# Sensors_and_Actuators.net
KiCad netlist of a schematic drawn in Altium Designer
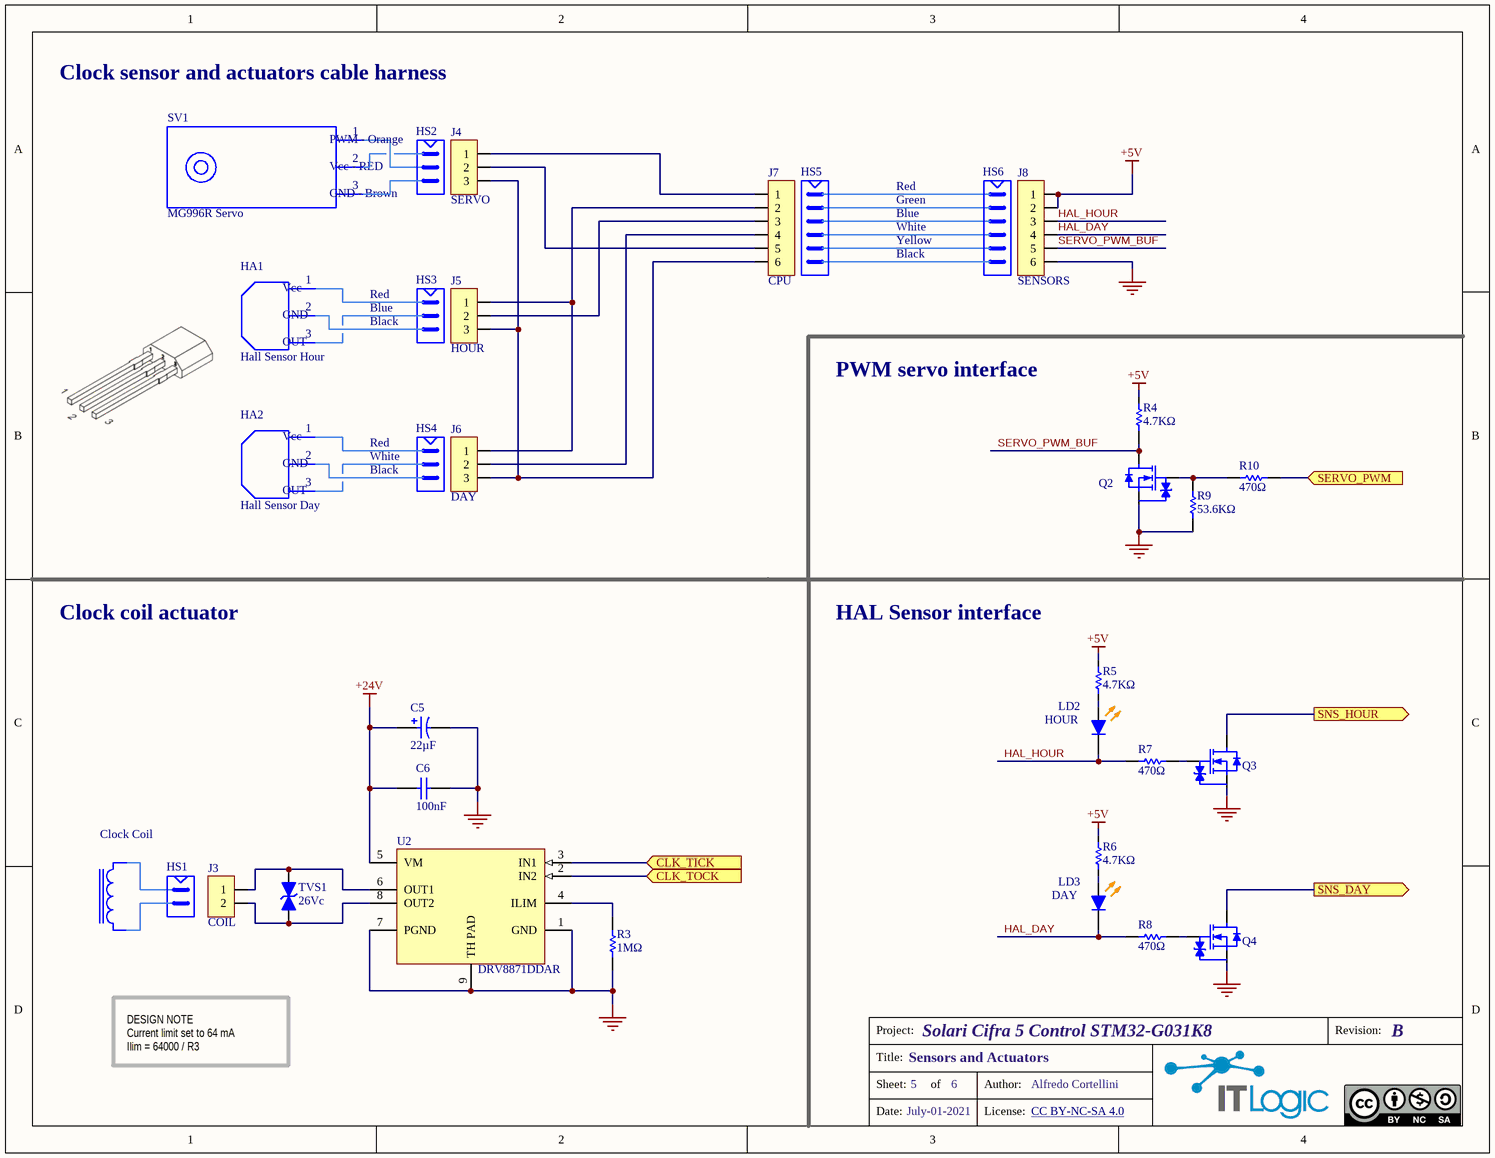
[diagram p0: Sensors and Actuators.SchDoc]

(export (version "E")
  (design (tool "Eeschema 10.0.6"))
  (components
    (comp (ref "C5")
      (value "22µF")
      (footprint "C-AE-C6-H60")
      (description "Cap Electrolytic Alu 22uF 50V 20% 165mA 2000h 105C Automotive, Case D")
      (fields
        (field (name "MANUFACTURER") "Panasonic")
        (field (name "MANUFACTURER PART NUMBER") "EEE-FK1H220P")
      )
      (libsource (lib "IT Logic Library") (part "EEE-FK1H220P"))
    )
    (comp (ref "C6")
      (value "100nF")
      (footprint "C0603-H90")
      (description "Cap 0603 Case Ceramic 100nF 50V X7R")
      (fields
        (field (name "MANUFACTURER") "TDK")
        (field (name "MANUFACTURER PART NUMBER") "CGA3E2X7R1H104K080AA")
      )
      (libsource (lib "IT Logic Library") (part "CGA3E2X7R1H104K080AA"))
    )
    (comp (ref "HA1")
      (value "Hall Sensor Hour")
      (description "Hall Effect/Magnetic Sensors 2.5 to 38 V 3-TO-92")
      (fields
        (field (name "MANUFACTURER") "Texas Instruments")
        (field (name "MANUFACTURER PART NUMBER") "DRV5023AJQLPG")
      )
      (libsource (lib "IT Logic Library") (part "DRV5023AJQLPG_MEC"))
    )
    (comp (ref "HA2")
      (value "Hall Sensor Day")
      (description "Hall Effect/Magnetic Sensors 2.5 to 38 V 3-TO-92")
      (fields
        (field (name "MANUFACTURER") "Texas Instruments")
        (field (name "MANUFACTURER PART NUMBER") "DRV5023AJQLPG")
      )
      (libsource (lib "IT Logic Library") (part "DRV5023AJQLPG_MEC"))
    )
    (comp (ref "HS1")
      (value "XHP-2")
      (description "Conn Crimp Housing, Series JST XH, 2 Circuits")
      (fields (field (name "MANUFACTURER") "JST"))
      (libsource (lib "IT Logic Library") (part "XHP-2"))
    )
    (comp (ref "HS2")
      (value "XHP-3")
      (description "Conn Crimp Housing, Series JST XH, 3 Circuits")
      (fields (field (name "MANUFACTURER") "JST"))
      (libsource (lib "IT Logic Library") (part "XHP-3"))
    )
    (comp (ref "HS3")
      (value "XHP-3")
      (description "Conn Crimp Housing, Series JST XH, 3 Circuits")
      (fields (field (name "MANUFACTURER") "JST"))
      (libsource (lib "IT Logic Library") (part "XHP-3"))
    )
    (comp (ref "HS4")
      (value "XHP-3")
      (description "Conn Crimp Housing, Series JST XH, 3 Circuits")
      (fields (field (name "MANUFACTURER") "JST"))
      (libsource (lib "IT Logic Library") (part "XHP-3"))
    )
    (comp (ref "HS5")
      (value "XHP-6")
      (description "Conn Crimp Housing, Series JST XH, 6 Circuits")
      (fields (field (name "MANUFACTURER") "JST"))
      (libsource (lib "IT Logic Library") (part "XHP-6"))
    )
    (comp (ref "HS6")
      (value "XHP-6")
      (description "Conn Crimp Housing, Series JST XH, 6 Circuits")
      (fields (field (name "MANUFACTURER") "JST"))
      (libsource (lib "IT Logic Library") (part "XHP-6"))
    )
    (comp (ref "J3")
      (value "COIL")
      (footprint "JST B2B-XH-A")
      (description "Conn Shrouded, Series JST XH, 2 Pos Header,(2.50mm) Through Hole, Vertical Tin")
      (fields
        (field (name "MANUFACTURER") "JST")
        (field (name "MANUFACTURER PART NUMBER") "B2B-XH-A(LF)(SN)")
      )
      (libsource (lib "IT Logic Library") (part "B2B-XH-A(LF)(SN)"))
    )
    (comp (ref "J4")
      (value "SERVO")
      (footprint "JST B3B-XH-A")
      (description "Conn Shrouded, Series JST XH, 3 Pos Header,(2.50mm) Through Hole, Vertical Tin")
      (fields
        (field (name "MANUFACTURER") "JST")
        (field (name "MANUFACTURER PART NUMBER") "B3B-XH-A(LF)(SN)")
      )
      (libsource (lib "IT Logic Library") (part "B3B-XH-A(LF)(SN)"))
    )
    (comp (ref "J5")
      (value "HOUR")
      (footprint "JST B3B-XH-A")
      (description "Conn Shrouded, Series JST XH, 3 Pos Header,(2.50mm) Through Hole, Vertical Tin")
      (fields
        (field (name "MANUFACTURER") "JST")
        (field (name "MANUFACTURER PART NUMBER") "B3B-XH-A(LF)(SN)")
      )
      (libsource (lib "IT Logic Library") (part "B3B-XH-A(LF)(SN)"))
    )
    (comp (ref "J6")
      (value "DAY")
      (footprint "JST B3B-XH-A")
      (description "Conn Shrouded, Series JST XH, 3 Pos Header,(2.50mm) Through Hole, Vertical Tin")
      (fields
        (field (name "MANUFACTURER") "JST")
        (field (name "MANUFACTURER PART NUMBER") "B3B-XH-A(LF)(SN)")
      )
      (libsource (lib "IT Logic Library") (part "B3B-XH-A(LF)(SN)"))
    )
    (comp (ref "J7")
      (value "CPU")
      (footprint "JST B6B-XH-A")
      (description "Conn Shrouded, Series JST XH, 6 Pos Header, (2.50mm) Through Hole, Vertical Tin")
      (fields
        (field (name "MANUFACTURER") "JST")
        (field (name "MANUFACTURER PART NUMBER") "B6B-XH-A(LF)(SN)")
      )
      (libsource (lib "IT Logic Library") (part "B6B-XH-A(LF)(SN)"))
    )
    (comp (ref "J8")
      (value "SENSORS")
      (footprint "JST B6B-XH-A")
      (description "Conn Shrouded, Series JST XH, 6 Pos Header, (2.50mm) Through Hole, Vertical Tin")
      (fields
        (field (name "MANUFACTURER") "JST")
        (field (name "MANUFACTURER PART NUMBER") "B6B-XH-A(LF)(SN)")
      )
      (libsource (lib "") (part "B6B-XH-A(LF)(SN)_1"))
    )
    (comp (ref "LD2")
      (value "HOUR")
      (footprint "LED-0805-O")
      (description "LED 0805 Top Orange 605nm 2-Pin")
      (fields
        (field (name "MANUFACTURER") "Vishay Lite-On")
        (field (name "MANUFACTURER PART NUMBER") "LTST-C170KFKT")
      )
      (libsource (lib "IT Logic Library") (part "LTST-C170KFKT"))
    )
    (comp (ref "LD3")
      (value "DAY")
      (footprint "LED-0805-O")
      (description "LED 0805 Top Orange 605nm 2-Pin")
      (fields
        (field (name "MANUFACTURER") "Vishay Lite-On")
        (field (name "MANUFACTURER PART NUMBER") "LTST-C170KFKT")
      )
      (libsource (lib "IT Logic Library") (part "LTST-C170KFKT"))
    )
    (comp (ref "Q2")
      (value "BSS138K-13")
      (footprint "SOT-23")
      (description "Mosfet N 50V Vds 20V Vgs ESD 1.4R SOT-23")
      (fields (field (name "MANUFACTURER") "Diodes"))
      (libsource (lib "IT Logic Library") (part "BSS138K-13"))
    )
    (comp (ref "Q3")
      (value "BSS138K-13")
      (footprint "SOT-23")
      (description "Mosfet N 50V Vds 20V Vgs ESD 1.4R SOT-23")
      (fields (field (name "MANUFACTURER") "Diodes"))
      (libsource (lib "IT Logic Library") (part "BSS138K-13"))
    )
    (comp (ref "Q4")
      (value "BSS138K-13")
      (footprint "SOT-23")
      (description "Mosfet N 50V Vds 20V Vgs ESD 1.4R SOT-23")
      (fields (field (name "MANUFACTURER") "Diodes"))
      (libsource (lib "IT Logic Library") (part "BSS138K-13"))
    )
    (comp (ref "R3")
      (value "1MΩ")
      (footprint "R0603-H55")
      (description "Resistor 0603 Case 1MR 1% 1/10W")
      (fields
        (field (name "MANUFACTURER") "Yageo")
        (field (name "MANUFACTURER PART NUMBER") "RC0603FR-071ML")
      )
      (libsource (lib "IT Logic Library") (part "RC0603FR-071ML"))
    )
    (comp (ref "R4")
      (value "4.7KΩ")
      (footprint "R0603-H55")
      (description "Resistor 0603 Case 4.7KR 1% 1/10W")
      (fields
        (field (name "MANUFACTURER") "Yageo")
        (field (name "MANUFACTURER PART NUMBER") "RC0603FR-074K7L")
      )
      (libsource (lib "IT Logic Library") (part "RC0603FR-074K7L"))
    )
    (comp (ref "R5")
      (value "4.7KΩ")
      (footprint "R0603-H55")
      (description "Resistor 0603 Case 4.7KR 1% 1/10W")
      (fields
        (field (name "MANUFACTURER") "Yageo")
        (field (name "MANUFACTURER PART NUMBER") "RC0603FR-074K7L")
      )
      (libsource (lib "IT Logic Library") (part "RC0603FR-074K7L"))
    )
    (comp (ref "R6")
      (value "4.7KΩ")
      (footprint "R0603-H55")
      (description "Resistor 0603 Case 4.7KR 1% 1/10W")
      (fields
        (field (name "MANUFACTURER") "Yageo")
        (field (name "MANUFACTURER PART NUMBER") "RC0603FR-074K7L")
      )
      (libsource (lib "IT Logic Library") (part "RC0603FR-074K7L"))
    )
    (comp (ref "R7")
      (value "470Ω")
      (footprint "R0603-H55")
      (description "Resistor 0603 Case 470R 1% 1/10W")
      (fields
        (field (name "MANUFACTURER") "Yageo")
        (field (name "MANUFACTURER PART NUMBER") "RC0603FR-07470RL")
      )
      (libsource (lib "IT Logic Library") (part "RC0603FR-07470RL"))
    )
    (comp (ref "R8")
      (value "470Ω")
      (footprint "R0603-H55")
      (description "Resistor 0603 Case 470R 1% 1/10W")
      (fields
        (field (name "MANUFACTURER") "Yageo")
        (field (name "MANUFACTURER PART NUMBER") "RC0603FR-07470RL")
      )
      (libsource (lib "IT Logic Library") (part "RC0603FR-07470RL"))
    )
    (comp (ref "R9")
      (value "53.6KΩ")
      (footprint "R0603-H55")
      (description "Resistor 0603 Case 53.6KR 1% 1/10W")
      (fields
        (field (name "MANUFACTURER") "Yageo")
        (field (name "MANUFACTURER PART NUMBER") "RC0603FR-0753K6L")
      )
      (libsource (lib "IT Logic Library") (part "RC0603FR-0753K6L"))
    )
    (comp (ref "R10")
      (value "470Ω")
      (footprint "R0603-H55")
      (description "Resistor 0603 Case 470R 1% 1/10W")
      (fields
        (field (name "MANUFACTURER") "Yageo")
        (field (name "MANUFACTURER PART NUMBER") "RC0603FR-07470RL")
      )
      (libsource (lib "IT Logic Library") (part "RC0603FR-07470RL"))
    )
    (comp (ref "SV1")
      (value "MG996R Servo")
      (description "Servo, High Torque, Metal Gear, Dual Ball Bearing, 120 Gegrees, Stall torque: 9.4 kgf·cm (4.8V),")
      (fields (field (name "MANUFACTURER") "Jajadeal") (field (name "MANUFACTURER PART NUMBER") "MG996R"))
      (libsource (lib "IT Logic Library") (part "MG996R"))
    )
    (comp (ref "TF1")
      (value "SXH-001T-P0.6")
      (description "Crimp Terminal, Series JST XH, Female, 22-28 AWG,")
      (fields (field (name "MANUFACTURER") "JST"))
      (libsource (lib "IT Logic Library") (part "SXH-001T-P0.6"))
    )
    (comp (ref "TF2")
      (value "SXH-001T-P0.6")
      (description "Crimp Terminal, Series JST XH, Female, 22-28 AWG,")
      (fields (field (name "MANUFACTURER") "JST"))
      (libsource (lib "IT Logic Library") (part "SXH-001T-P0.6"))
    )
    (comp (ref "TF3")
      (value "SXH-001T-P0.6")
      (description "Crimp Terminal, Series JST XH, Female, 22-28 AWG,")
      (fields (field (name "MANUFACTURER") "JST"))
      (libsource (lib "IT Logic Library") (part "SXH-001T-P0.6"))
    )
    (comp (ref "TF4")
      (value "SXH-001T-P0.6")
      (description "Crimp Terminal, Series JST XH, Female, 22-28 AWG,")
      (fields (field (name "MANUFACTURER") "JST"))
      (libsource (lib "IT Logic Library") (part "SXH-001T-P0.6"))
    )
    (comp (ref "TF5")
      (value "SXH-001T-P0.6")
      (description "Crimp Terminal, Series JST XH, Female, 22-28 AWG,")
      (fields (field (name "MANUFACTURER") "JST"))
      (libsource (lib "IT Logic Library") (part "SXH-001T-P0.6"))
    )
    (comp (ref "TF6")
      (value "SXH-001T-P0.6")
      (description "Crimp Terminal, Series JST XH, Female, 22-28 AWG,")
      (fields (field (name "MANUFACTURER") "JST"))
      (libsource (lib "IT Logic Library") (part "SXH-001T-P0.6"))
    )
    (comp (ref "TF7")
      (value "SXH-001T-P0.6")
      (description "Crimp Terminal, Series JST XH, Female, 22-28 AWG,")
      (fields (field (name "MANUFACTURER") "JST"))
      (libsource (lib "IT Logic Library") (part "SXH-001T-P0.6"))
    )
    (comp (ref "TF8")
      (value "SXH-001T-P0.6")
      (description "Crimp Terminal, Series JST XH, Female, 22-28 AWG,")
      (fields (field (name "MANUFACTURER") "JST"))
      (libsource (lib "IT Logic Library") (part "SXH-001T-P0.6"))
    )
    (comp (ref "TF9")
      (value "SXH-001T-P0.6")
      (description "Crimp Terminal, Series JST XH, Female, 22-28 AWG,")
      (fields (field (name "MANUFACTURER") "JST"))
      (libsource (lib "IT Logic Library") (part "SXH-001T-P0.6"))
    )
    (comp (ref "TF10")
      (value "SXH-001T-P0.6")
      (description "Crimp Terminal, Series JST XH, Female, 22-28 AWG,")
      (fields (field (name "MANUFACTURER") "JST"))
      (libsource (lib "IT Logic Library") (part "SXH-001T-P0.6"))
    )
    (comp (ref "TF11")
      (value "SXH-001T-P0.6")
      (description "Crimp Terminal, Series JST XH, Female, 22-28 AWG,")
      (fields (field (name "MANUFACTURER") "JST"))
      (libsource (lib "IT Logic Library") (part "SXH-001T-P0.6"))
    )
    (comp (ref "TF12")
      (value "SXH-001T-P0.6")
      (description "Crimp Terminal, Series JST XH, Female, 22-28 AWG,")
      (fields (field (name "MANUFACTURER") "JST"))
      (libsource (lib "IT Logic Library") (part "SXH-001T-P0.6"))
    )
    (comp (ref "TF13")
      (value "SXH-001T-P0.6")
      (description "Crimp Terminal, Series JST XH, Female, 22-28 AWG,")
      (fields (field (name "MANUFACTURER") "JST"))
      (libsource (lib "IT Logic Library") (part "SXH-001T-P0.6"))
    )
    (comp (ref "TF14")
      (value "SXH-001T-P0.6")
      (description "Crimp Terminal, Series JST XH, Female, 22-28 AWG,")
      (fields (field (name "MANUFACTURER") "JST"))
      (libsource (lib "IT Logic Library") (part "SXH-001T-P0.6"))
    )
    (comp (ref "TF15")
      (value "SXH-001T-P0.6")
      (description "Crimp Terminal, Series JST XH, Female, 22-28 AWG,")
      (fields (field (name "MANUFACTURER") "JST"))
      (libsource (lib "IT Logic Library") (part "SXH-001T-P0.6"))
    )
    (comp (ref "TF16")
      (value "SXH-001T-P0.6")
      (description "Crimp Terminal, Series JST XH, Female, 22-28 AWG,")
      (fields (field (name "MANUFACTURER") "JST"))
      (libsource (lib "IT Logic Library") (part "SXH-001T-P0.6"))
    )
    (comp (ref "TF17")
      (value "SXH-001T-P0.6")
      (description "Crimp Terminal, Series JST XH, Female, 22-28 AWG,")
      (fields (field (name "MANUFACTURER") "JST"))
      (libsource (lib "IT Logic Library") (part "SXH-001T-P0.6"))
    )
    (comp (ref "TF18")
      (value "SXH-001T-P0.6")
      (description "Crimp Terminal, Series JST XH, Female, 22-28 AWG,")
      (fields (field (name "MANUFACTURER") "JST"))
      (libsource (lib "IT Logic Library") (part "SXH-001T-P0.6"))
    )
    (comp (ref "TF19")
      (value "SXH-001T-P0.6")
      (description "Crimp Terminal, Series JST XH, Female, 22-28 AWG,")
      (fields (field (name "MANUFACTURER") "JST"))
      (libsource (lib "IT Logic Library") (part "SXH-001T-P0.6"))
    )
    (comp (ref "TF20")
      (value "SXH-001T-P0.6")
      (description "Crimp Terminal, Series JST XH, Female, 22-28 AWG,")
      (fields (field (name "MANUFACTURER") "JST"))
      (libsource (lib "IT Logic Library") (part "SXH-001T-P0.6"))
    )
    (comp (ref "TF21")
      (value "SXH-001T-P0.6")
      (description "Crimp Terminal, Series JST XH, Female, 22-28 AWG,")
      (fields (field (name "MANUFACTURER") "JST"))
      (libsource (lib "IT Logic Library") (part "SXH-001T-P0.6"))
    )
    (comp (ref "TF22")
      (value "SXH-001T-P0.6")
      (description "Crimp Terminal, Series JST XH, Female, 22-28 AWG,")
      (fields (field (name "MANUFACTURER") "JST"))
      (libsource (lib "IT Logic Library") (part "SXH-001T-P0.6"))
    )
    (comp (ref "TF23")
      (value "SXH-001T-P0.6")
      (description "Crimp Terminal, Series JST XH, Female, 22-28 AWG,")
      (fields (field (name "MANUFACTURER") "JST"))
      (libsource (lib "IT Logic Library") (part "SXH-001T-P0.6"))
    )
    (comp (ref "TVS1")
      (value "26Vc")
      (footprint "DO-214AC-SMA-NO POL")
      (description "TVS Diode Bidirectional 26Vs, 42.1Vc, 9.5 Amp, SMA")
      (fields (field (name "MANUFACTURER") "Littelfuse") (field (name "MANUFACTURER PART NUMBER") "SMAJ26CA"))
      (libsource (lib "IT Logic Library") (part "SMAJ26CA"))
    )
    (comp (ref "U2")
      (value "DRV8871DDAR")
      (footprint "SOIC-8-N-HT")
      (description "Motor Driver H-bridge 45V, 3.6A, Integrated current sensing SOIC-8 PowerPAD -40 to 125")
      (fields (field (name "MANUFACTURER") "Texas Instruments"))
      (libsource (lib "IT Logic Library") (part "DRV8871DDAR"))
    )
  )
  (nets
    (net (code "1") (name "+5V") (class "Default")
      (node (ref "J8") (pin "1") (pinfunction "1_1") (pintype "passive"))
      (node (ref "J8") (pin "2") (pinfunction "2_2") (pintype "passive"))
      (node (ref "R4") (pin "2") (pinfunction "2_2") (pintype "passive"))
      (node (ref "R5") (pin "2") (pinfunction "2_2") (pintype "passive"))
      (node (ref "R6") (pin "2") (pinfunction "2_2") (pintype "passive"))
    )
    (net (code "2") (name "+24V") (class "Default")
      (node (ref "C5") (pin "1") (pinfunction "1_1") (pintype "passive"))
      (node (ref "C6") (pin "1") (pinfunction "1_1") (pintype "passive"))
      (node (ref "U2") (pin "5") (pinfunction "VM_5") (pintype "power_in"))
    )
    (net (code "3") (name "/CLK_TICK") (class "Default")
      (node (ref "U2") (pin "3") (pinfunction "IN1_3") (pintype "input"))
    )
    (net (code "4") (name "/CLK_TOCK") (class "Default")
      (node (ref "U2") (pin "2") (pinfunction "IN2_2") (pintype "input"))
    )
    (net (code "5") (name "/HAL_DAY") (class "Default")
      (node (ref "J8") (pin "4") (pinfunction "4_4") (pintype "passive"))
      (node (ref "LD3") (pin "1") (pinfunction "K_1") (pintype "passive"))
      (node (ref "R8") (pin "1") (pinfunction "1_1") (pintype "passive"))
    )
    (net (code "6") (name "/HAL_HOUR") (class "Default")
      (node (ref "J8") (pin "3") (pinfunction "3_3") (pintype "passive"))
      (node (ref "LD2") (pin "1") (pinfunction "K_1") (pintype "passive"))
      (node (ref "R7") (pin "1") (pinfunction "1_1") (pintype "passive"))
    )
    (net (code "7") (name "/SERVO_PWM") (class "Default")
      (node (ref "R10") (pin "2") (pinfunction "2_2") (pintype "passive"))
    )
    (net (code "8") (name "/SERVO_PWM_BUF") (class "Default")
      (node (ref "J8") (pin "5") (pinfunction "5_5") (pintype "passive"))
      (node (ref "Q2") (pin "3") (pinfunction "D_3") (pintype "passive"))
      (node (ref "R4") (pin "1") (pinfunction "1_1") (pintype "passive"))
    )
    (net (code "9") (name "/SNS_DAY") (class "Default")
      (node (ref "Q4") (pin "3") (pinfunction "D_3") (pintype "passive"))
    )
    (net (code "10") (name "/SNS_HOUR") (class "Default")
      (node (ref "Q3") (pin "3") (pinfunction "D_3") (pintype "passive"))
    )
    (net (code "11") (name "GND") (class "Default")
      (node (ref "C5") (pin "2") (pinfunction "2_2") (pintype "passive"))
      (node (ref "C6") (pin "2") (pinfunction "2_2") (pintype "passive"))
      (node (ref "J8") (pin "6") (pinfunction "6_6") (pintype "passive"))
      (node (ref "Q2") (pin "2") (pinfunction "S_2") (pintype "passive"))
      (node (ref "Q3") (pin "2") (pinfunction "S_2") (pintype "passive"))
      (node (ref "Q4") (pin "2") (pinfunction "S_2") (pintype "passive"))
      (node (ref "R3") (pin "1") (pinfunction "1_1") (pintype "passive"))
      (node (ref "R9") (pin "1") (pinfunction "1_1") (pintype "passive"))
      (node (ref "U2") (pin "1") (pinfunction "GND_1") (pintype "power_in"))
      (node (ref "U2") (pin "7") (pinfunction "PGND_7") (pintype "power_in"))
      (node (ref "U2") (pin "9") (pinfunction "TH_PAD_9") (pintype "power_in"))
    )
    (net (code "12") (name "Net-(J4-Pad1)") (class "Default")
      (node (ref "J4") (pin "1") (pinfunction "1_1") (pintype "passive"))
      (node (ref "J7") (pin "1") (pinfunction "1_1") (pintype "passive"))
    )
    (net (code "13") (name "Net-(J4-Pad2)") (class "Default")
      (node (ref "J4") (pin "2") (pinfunction "2_2") (pintype "passive"))
      (node (ref "J7") (pin "5") (pinfunction "5_5") (pintype "passive"))
    )
    (net (code "14") (name "Net-(J4-Pad3)") (class "Default")
      (node (ref "J4") (pin "3") (pinfunction "3_3") (pintype "passive"))
      (node (ref "J5") (pin "3") (pinfunction "3_3") (pintype "passive"))
      (node (ref "J6") (pin "3") (pinfunction "3_3") (pintype "passive"))
      (node (ref "J7") (pin "6") (pinfunction "6_6") (pintype "passive"))
    )
    (net (code "15") (name "Net-(J5-Pad1)") (class "Default")
      (node (ref "J5") (pin "1") (pinfunction "1_1") (pintype "passive"))
      (node (ref "J6") (pin "1") (pinfunction "1_1") (pintype "passive"))
      (node (ref "J7") (pin "2") (pinfunction "2_2") (pintype "passive"))
    )
    (net (code "16") (name "Net-(J5-Pad2)") (class "Default")
      (node (ref "J5") (pin "2") (pinfunction "2_2") (pintype "passive"))
      (node (ref "J7") (pin "3") (pinfunction "3_3") (pintype "passive"))
    )
    (net (code "17") (name "Net-(J6-Pad2)") (class "Default")
      (node (ref "J6") (pin "2") (pinfunction "2_2") (pintype "passive"))
      (node (ref "J7") (pin "4") (pinfunction "4_4") (pintype "passive"))
    )
    (net (code "18") (name "Net-(LD2-A)") (class "Default")
      (node (ref "LD2") (pin "2") (pinfunction "A_2") (pintype "passive"))
      (node (ref "R5") (pin "1") (pinfunction "1_1") (pintype "passive"))
    )
    (net (code "19") (name "Net-(LD3-A)") (class "Default")
      (node (ref "LD3") (pin "2") (pinfunction "A_2") (pintype "passive"))
      (node (ref "R6") (pin "1") (pinfunction "1_1") (pintype "passive"))
    )
    (net (code "20") (name "Net-(Q2-G)") (class "Default")
      (node (ref "Q2") (pin "1") (pinfunction "G_1") (pintype "passive"))
      (node (ref "R10") (pin "1") (pinfunction "1_1") (pintype "passive"))
      (node (ref "R9") (pin "2") (pinfunction "2_2") (pintype "passive"))
    )
    (net (code "21") (name "Net-(Q3-G)") (class "Default")
      (node (ref "Q3") (pin "1") (pinfunction "G_1") (pintype "passive"))
      (node (ref "R7") (pin "2") (pinfunction "2_2") (pintype "passive"))
    )
    (net (code "22") (name "Net-(Q4-G)") (class "Default")
      (node (ref "Q4") (pin "1") (pinfunction "G_1") (pintype "passive"))
      (node (ref "R8") (pin "2") (pinfunction "2_2") (pintype "passive"))
    )
    (net (code "23") (name "Net-(U2-ILIM)") (class "Default")
      (node (ref "R3") (pin "2") (pinfunction "2_2") (pintype "passive"))
      (node (ref "U2") (pin "4") (pinfunction "ILIM_4") (pintype "passive"))
    )
    (net (code "24") (name "Net-(U2-OUT1)") (class "Default")
      (node (ref "J3") (pin "1") (pinfunction "1_1") (pintype "passive"))
      (node (ref "TVS1") (pin "2") (pinfunction "2_2") (pintype "passive"))
      (node (ref "U2") (pin "6") (pinfunction "OUT1_6") (pintype "passive"))
    )
    (net (code "25") (name "Net-(U2-OUT2)") (class "Default")
      (node (ref "J3") (pin "2") (pinfunction "2_2") (pintype "passive"))
      (node (ref "TVS1") (pin "1") (pinfunction "1_1") (pintype "passive"))
      (node (ref "U2") (pin "8") (pinfunction "OUT2_8") (pintype "passive"))
    )
  )
)
